# MCU.net
KiCad netlist of a schematic drawn in Altium Designer
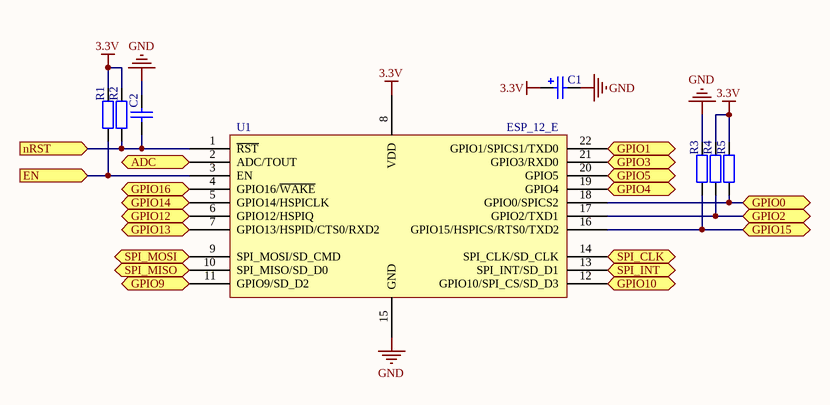
[diagram p0: MCU.SchDoc]

(export (version "E")
  (design (tool "Eeschema 10.0.6"))
  (components
    (comp (ref "C1")
      (value "100uF")
      (footprint "CASE-B_3528")
      (description "贴片电容-有极性")
      (libsource (lib "Power_Lib_Altium") (part "CAP-POL"))
    )
    (comp (ref "C2")
      (value "100nF")
      (footprint "CAP-0603")
      (description "贴片电容")
      (libsource (lib "Power_Lib_Altium") (part "CAP"))
    )
    (comp (ref "R1")
      (value "12K")
      (footprint "R-0603")
      (description "贴片电阻")
      (libsource (lib "Power_Lib_Altium") (part "RES"))
    )
    (comp (ref "R2")
      (value "12K")
      (footprint "R-0603")
      (description "贴片电阻")
      (libsource (lib "Power_Lib_Altium") (part "RES"))
    )
    (comp (ref "R3")
      (value "12K")
      (footprint "R-0603")
      (description "贴片电阻")
      (libsource (lib "Power_Lib_Altium") (part "RES"))
    )
    (comp (ref "R4")
      (value "12K")
      (footprint "R-0603")
      (description "贴片电阻")
      (libsource (lib "Power_Lib_Altium") (part "RES"))
    )
    (comp (ref "R5")
      (value "12K")
      (footprint "R-0603")
      (description "贴片电阻")
      (libsource (lib "Power_Lib_Altium") (part "RES"))
    )
    (comp (ref "U1")
      (value "ESP_12_E")
      (footprint "ESP_12_E_L")
      (description "ESP-12 Wi-Fi Module by AI-Thinker")
      (libsource (lib "Power_Lib_Altium") (part "ESP_12_E"))
    )
  )
  (nets
    (net (code "1") (name "/ADC") (class "Default")
      (node (ref "U1") (pin "2") (pinfunction "ADC/TOUT_2") (pintype "passive"))
    )
    (net (code "2") (name "/EN") (class "Default")
      (node (ref "R1") (pin "1") (pinfunction "1_1") (pintype "passive"))
      (node (ref "U1") (pin "3") (pinfunction "EN_3") (pintype "passive"))
    )
    (net (code "3") (name "/GPIO0") (class "Default")
      (node (ref "R5") (pin "1") (pinfunction "1_1") (pintype "passive"))
      (node (ref "U1") (pin "18") (pinfunction "GPIO0/SPICS2_18") (pintype "passive"))
    )
    (net (code "4") (name "/GPIO1") (class "Default")
      (node (ref "U1") (pin "22") (pinfunction "GPIO1/SPICS1/TXD0_22") (pintype "passive"))
    )
    (net (code "5") (name "/GPIO2") (class "Default")
      (node (ref "R4") (pin "1") (pinfunction "1_1") (pintype "passive"))
      (node (ref "U1") (pin "17") (pinfunction "GPIO2/TXD1_17") (pintype "passive"))
    )
    (net (code "6") (name "/GPIO3") (class "Default")
      (node (ref "U1") (pin "21") (pinfunction "GPIO3/RXD0_21") (pintype "passive"))
    )
    (net (code "7") (name "/GPIO4") (class "Default")
      (node (ref "U1") (pin "19") (pinfunction "GPIO4_19") (pintype "passive"))
    )
    (net (code "8") (name "/GPIO5") (class "Default")
      (node (ref "U1") (pin "20") (pinfunction "GPIO5_20") (pintype "passive"))
    )
    (net (code "9") (name "/GPIO9") (class "Default")
      (node (ref "U1") (pin "11") (pinfunction "GPIO9/SD_D2_11") (pintype "passive"))
    )
    (net (code "10") (name "/GPIO10") (class "Default")
      (node (ref "U1") (pin "12") (pinfunction "GPIO10/SPI_CS/SD_D3_12") (pintype "passive"))
    )
    (net (code "11") (name "/GPIO12") (class "Default")
      (node (ref "U1") (pin "6") (pinfunction "GPIO12/HSPIQ_6") (pintype "passive"))
    )
    (net (code "12") (name "/GPIO13") (class "Default")
      (node (ref "U1") (pin "7") (pinfunction "GPIO13/HSPID/CTS0/RXD2_7") (pintype "passive"))
    )
    (net (code "13") (name "/GPIO14") (class "Default")
      (node (ref "U1") (pin "5") (pinfunction "GPIO14/HSPICLK_5") (pintype "passive"))
    )
    (net (code "14") (name "/GPIO15") (class "Default")
      (node (ref "R3") (pin "1") (pinfunction "1_1") (pintype "passive"))
      (node (ref "U1") (pin "16") (pinfunction "GPIO15/HSPICS/RTS0/TXD2_16") (pintype "passive"))
    )
    (net (code "15") (name "/GPIO16") (class "Default")
      (node (ref "U1") (pin "4") (pinfunction "GPIO16/~{WAKE}_4") (pintype "passive"))
    )
    (net (code "16") (name "/SPI_CLK") (class "Default")
      (node (ref "U1") (pin "14") (pinfunction "SPI_CLK/SD_CLK_14") (pintype "passive"))
    )
    (net (code "17") (name "/SPI_INT") (class "Default")
      (node (ref "U1") (pin "13") (pinfunction "SPI_INT/SD_D1_13") (pintype "passive"))
    )
    (net (code "18") (name "/SPI_MISO") (class "Default")
      (node (ref "U1") (pin "10") (pinfunction "SPI_MISO/SD_D0_10") (pintype "passive"))
    )
    (net (code "19") (name "/SPI_MOSI") (class "Default")
      (node (ref "U1") (pin "9") (pinfunction "SPI_MOSI/SD_CMD_9") (pintype "passive"))
    )
    (net (code "20") (name "/nRST") (class "Default")
      (node (ref "C2") (pin "1") (pinfunction "1_1") (pintype "passive"))
      (node (ref "R2") (pin "1") (pinfunction "1_1") (pintype "passive"))
      (node (ref "U1") (pin "1") (pinfunction "~{RST}_1") (pintype "passive"))
    )
    (net (code "21") (name "3.3V") (class "Default")
      (node (ref "C1") (pin "1") (pinfunction "1_1") (pintype "passive"))
      (node (ref "R1") (pin "2") (pinfunction "2_2") (pintype "passive"))
      (node (ref "R2") (pin "2") (pinfunction "2_2") (pintype "passive"))
      (node (ref "R4") (pin "2") (pinfunction "2_2") (pintype "passive"))
      (node (ref "R5") (pin "2") (pinfunction "2_2") (pintype "passive"))
      (node (ref "U1") (pin "8") (pinfunction "VDD_8") (pintype "passive"))
    )
    (net (code "22") (name "GND") (class "Default")
      (node (ref "C1") (pin "2") (pinfunction "2_2") (pintype "passive"))
      (node (ref "C2") (pin "2") (pinfunction "2_2") (pintype "passive"))
      (node (ref "R3") (pin "2") (pinfunction "2_2") (pintype "passive"))
      (node (ref "U1") (pin "15") (pinfunction "GND_15") (pintype "passive"))
    )
  )
)
